# K60_main.net
KiCad netlist of a schematic drawn in Altium Designer
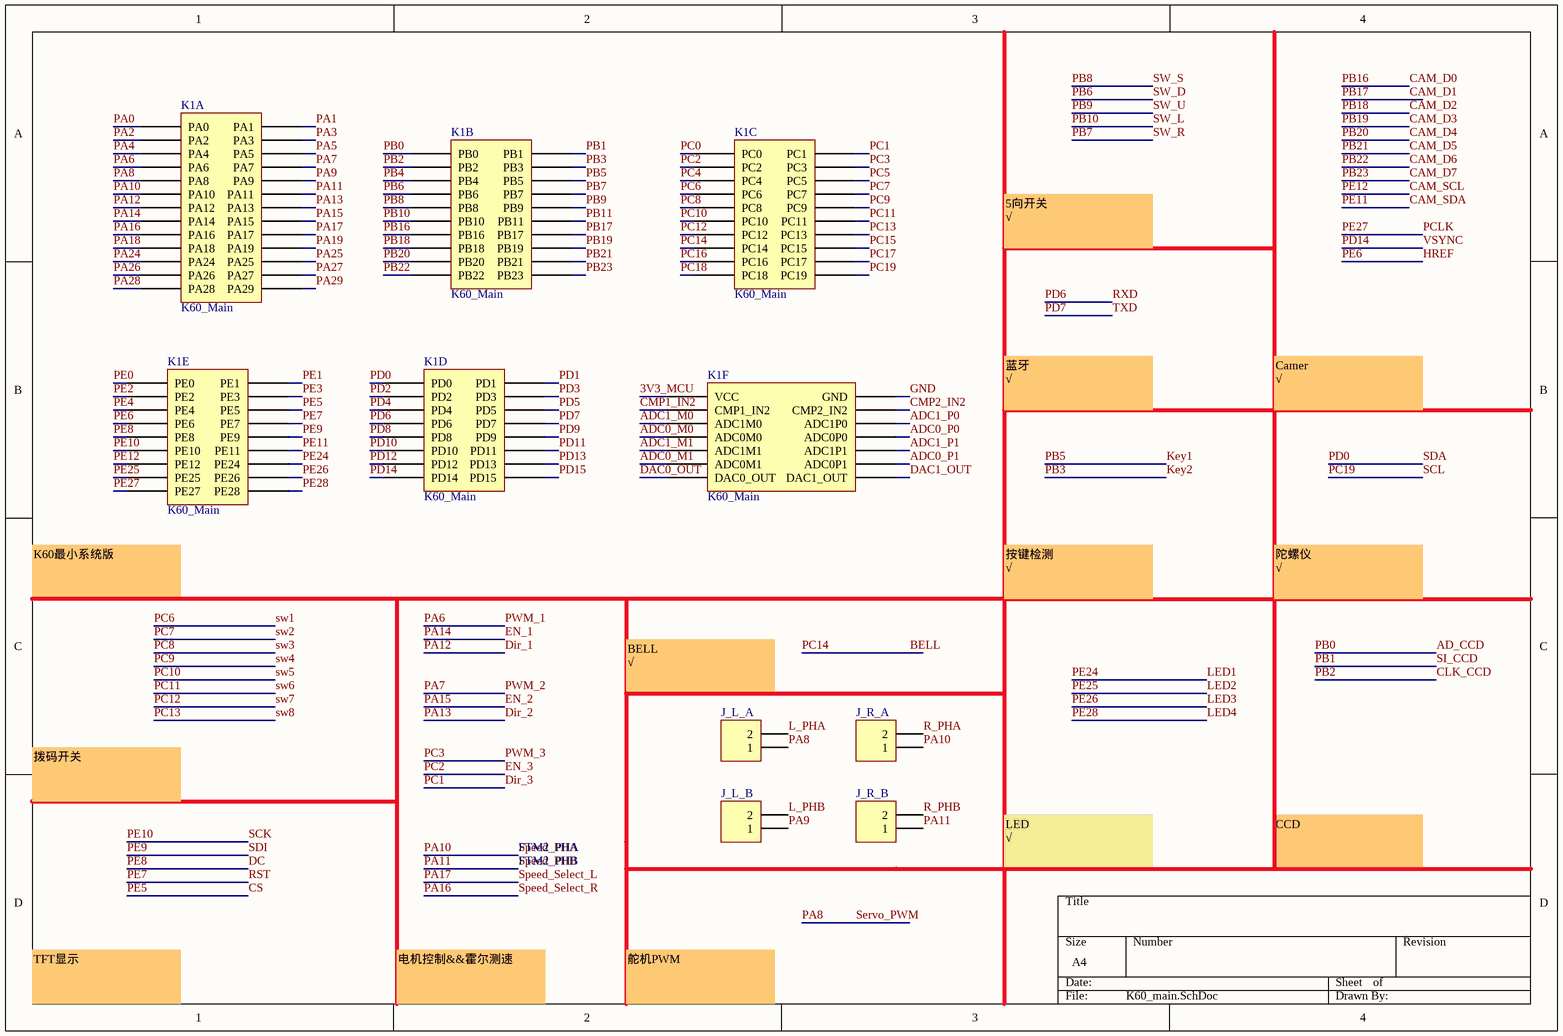
[diagram p0: K60_main.SchDoc]

(export (version "E")
  (design (tool "Eeschema 10.0.6"))
  (components
    (comp (ref "J_L_A")
      (value "Header 2")
      (footprint "HDR1X2")
      (description "Header, 2-Pin")
      (fields (field (name "PUBLISHER") "Altium Limited"))
      (libsource (lib "Miscellaneous Connectors") (part "Header 2"))
    )
    (comp (ref "J_L_B")
      (value "Header 2")
      (footprint "HDR1X2")
      (description "Header, 2-Pin")
      (fields (field (name "PUBLISHER") "Altium Limited"))
      (libsource (lib "Miscellaneous Connectors") (part "Header 2"))
    )
    (comp (ref "J_R_A")
      (value "Header 2")
      (footprint "HDR1X2")
      (description "Header, 2-Pin")
      (fields (field (name "PUBLISHER") "Altium Limited"))
      (libsource (lib "Miscellaneous Connectors") (part "Header 2"))
    )
    (comp (ref "J_R_B")
      (value "Header 2")
      (footprint "HDR1X2")
      (description "Header, 2-Pin")
      (fields (field (name "PUBLISHER") "Altium Limited"))
      (libsource (lib "Miscellaneous Connectors") (part "Header 2"))
    )
    (comp (ref "K1")
      (value "K60_Main")
      (footprint "K60_Main_Board")
      (libsource (lib "lichao_Library") (part "K60_Main"))
    )
  )
  (nets
    (net (code "1") (name "/3V3_MCU") (class "Default")
      (node (ref "K1") (pin "11") (pinfunction "VCC_11") (pintype "passive"))
    )
    (net (code "2") (name "/ADC0_M0") (class "Default")
      (node (ref "K1") (pin "23") (pinfunction "ADC0M0_23") (pintype "passive"))
    )
    (net (code "3") (name "/ADC0_M1") (class "Default")
      (node (ref "K1") (pin "27") (pinfunction "ADC0M1_27") (pintype "passive"))
    )
    (net (code "4") (name "/ADC0_P0") (class "Default")
      (node (ref "K1") (pin "24") (pinfunction "ADC0P0_24") (pintype "passive"))
    )
    (net (code "5") (name "/ADC0_P1") (class "Default")
      (node (ref "K1") (pin "28") (pinfunction "ADC0P1_28") (pintype "passive"))
    )
    (net (code "6") (name "/ADC1_M0") (class "Default")
      (node (ref "K1") (pin "21") (pinfunction "ADC1M0_21") (pintype "passive"))
    )
    (net (code "7") (name "/ADC1_M1") (class "Default")
      (node (ref "K1") (pin "25") (pinfunction "ADC1M1_25") (pintype "passive"))
    )
    (net (code "8") (name "/ADC1_P0") (class "Default")
      (node (ref "K1") (pin "22") (pinfunction "ADC1P0_22") (pintype "passive"))
    )
    (net (code "9") (name "/ADC1_P1") (class "Default")
      (node (ref "K1") (pin "26") (pinfunction "ADC1P1_26") (pintype "passive"))
    )
    (net (code "10") (name "/AD_CCD") (class "Default")
      (node (ref "K1") (pin "49") (pinfunction "PB0_49") (pintype "passive"))
    )
    (net (code "11") (name "/BELL") (class "Default")
      (node (ref "K1") (pin "35") (pinfunction "PC14_35") (pintype "passive"))
    )
    (net (code "12") (name "/CAM_D0") (class "Default")
      (node (ref "K1") (pin "327") (pinfunction "PB16_327") (pintype "passive"))
    )
    (net (code "13") (name "/CAM_D1") (class "Default")
      (node (ref "K1") (pin "326") (pinfunction "PB17_326") (pintype "passive"))
    )
    (net (code "14") (name "/CAM_D2") (class "Default")
      (node (ref "K1") (pin "325") (pinfunction "PB18_325") (pintype "passive"))
    )
    (net (code "15") (name "/CAM_D3") (class "Default")
      (node (ref "K1") (pin "324") (pinfunction "PB19_324") (pintype "passive"))
    )
    (net (code "16") (name "/CAM_D4") (class "Default")
      (node (ref "K1") (pin "323") (pinfunction "PB20_323") (pintype "passive"))
    )
    (net (code "17") (name "/CAM_D5") (class "Default")
      (node (ref "K1") (pin "322") (pinfunction "PB21_322") (pintype "passive"))
    )
    (net (code "18") (name "/CAM_D6") (class "Default")
      (node (ref "K1") (pin "321") (pinfunction "PB22_321") (pintype "passive"))
    )
    (net (code "19") (name "/CAM_D7") (class "Default")
      (node (ref "K1") (pin "320") (pinfunction "PB23_320") (pintype "passive"))
    )
    (net (code "20") (name "/CAM_SCL") (class "Default")
      (node (ref "K1") (pin "29") (pinfunction "PE12_29") (pintype "passive"))
    )
    (net (code "21") (name "/CAM_SDA") (class "Default")
      (node (ref "K1") (pin "210") (pinfunction "PE11_210") (pintype "passive"))
    )
    (net (code "22") (name "/CLK_CCD") (class "Default")
      (node (ref "K1") (pin "47") (pinfunction "PB2_47") (pintype "passive"))
    )
    (net (code "23") (name "/CMP1_IN2") (class "Default")
      (node (ref "K1") (pin "13") (pinfunction "CMP1_IN2_13") (pintype "passive"))
    )
    (net (code "24") (name "/CMP2_IN2") (class "Default")
      (node (ref "K1") (pin "14") (pinfunction "CMP2_IN2_14") (pintype "passive"))
    )
    (net (code "25") (name "/CS") (class "Default")
      (node (ref "K1") (pin "216") (pinfunction "PE5_216") (pintype "passive"))
    )
    (net (code "26") (name "/DAC0_OUT") (class "Default")
      (node (ref "K1") (pin "54") (pinfunction "DAC0_OUT_54") (pintype "passive"))
    )
    (net (code "27") (name "/DAC1_OUT") (class "Default")
      (node (ref "K1") (pin "53") (pinfunction "DAC1_OUT_53") (pintype "passive"))
    )
    (net (code "28") (name "/DC") (class "Default")
      (node (ref "K1") (pin "213") (pinfunction "PE8_213") (pintype "passive"))
    )
    (net (code "29") (name "/Dir_1") (class "Default")
      (node (ref "K1") (pin "423") (pinfunction "PA12_423") (pintype "passive"))
    )
    (net (code "30") (name "/Dir_2") (class "Default")
      (node (ref "K1") (pin "422") (pinfunction "PA13_422") (pintype "passive"))
    )
    (net (code "31") (name "/Dir_3") (class "Default")
      (node (ref "K1") (pin "318") (pinfunction "PC1_318") (pintype "passive"))
    )
    (net (code "32") (name "/EN_1") (class "Default")
      (node (ref "K1") (pin "421") (pinfunction "PA14_421") (pintype "passive"))
    )
    (net (code "33") (name "/EN_2") (class "Default")
      (node (ref "K1") (pin "420") (pinfunction "PA15_420") (pintype "passive"))
    )
    (net (code "34") (name "/EN_3") (class "Default")
      (node (ref "K1") (pin "317") (pinfunction "PC2_317") (pintype "passive"))
    )
    (net (code "35") (name "/GND") (class "Default")
      (node (ref "K1") (pin "12") (pinfunction "GND_12") (pintype "passive"))
    )
    (net (code "36") (name "/HREF") (class "Default")
      (node (ref "K1") (pin "215") (pinfunction "PE6_215") (pintype "passive"))
    )
    (net (code "37") (name "/Key1") (class "Default")
      (node (ref "K1") (pin "44") (pinfunction "PB5_44") (pintype "passive"))
    )
    (net (code "38") (name "/Key2") (class "Default")
      (node (ref "K1") (pin "46") (pinfunction "PB3_46") (pintype "passive"))
    )
    (net (code "39") (name "/LED1") (class "Default")
      (node (ref "K1") (pin "52") (pinfunction "PE24_52") (pintype "passive"))
    )
    (net (code "40") (name "/LED2") (class "Default")
      (node (ref "K1") (pin "51") (pinfunction "PE25_51") (pintype "passive"))
    )
    (net (code "41") (name "/LED3") (class "Default")
      (node (ref "K1") (pin "438") (pinfunction "PE26_438") (pintype "passive"))
    )
    (net (code "42") (name "/LED4") (class "Default")
      (node (ref "K1") (pin "436") (pinfunction "PE28_436") (pintype "passive"))
    )
    (net (code "43") (name "/L_PHA") (class "Default")
      (node (ref "J_L_A") (pin "2") (pinfunction "2_2") (pintype "passive"))
    )
    (net (code "44") (name "/L_PHB") (class "Default")
      (node (ref "J_L_B") (pin "2") (pinfunction "2_2") (pintype "passive"))
    )
    (net (code "45") (name "/PA0") (class "Default")
      (node (ref "K1") (pin "435") (pinfunction "PA0_435") (pintype "passive"))
    )
    (net (code "46") (name "/PA1") (class "Default")
      (node (ref "K1") (pin "434") (pinfunction "PA1_434") (pintype "passive"))
    )
    (net (code "47") (name "/PA2") (class "Default")
      (node (ref "K1") (pin "433") (pinfunction "PA2_433") (pintype "passive"))
    )
    (net (code "48") (name "/PA3") (class "Default")
      (node (ref "K1") (pin "432") (pinfunction "PA3_432") (pintype "passive"))
    )
    (net (code "49") (name "/PA4") (class "Default")
      (node (ref "K1") (pin "431") (pinfunction "PA4_431") (pintype "passive"))
    )
    (net (code "50") (name "/PA5") (class "Default")
      (node (ref "K1") (pin "430") (pinfunction "PA5_430") (pintype "passive"))
    )
    (net (code "51") (name "/PA6") (class "Default")
      (node (ref "K1") (pin "429") (pinfunction "PA6_429") (pintype "passive"))
    )
    (net (code "52") (name "/PA7") (class "Default")
      (node (ref "K1") (pin "428") (pinfunction "PA7_428") (pintype "passive"))
    )
    (net (code "53") (name "/PA8") (class "Default")
      (node (ref "J_L_A") (pin "1") (pinfunction "1_1") (pintype "passive"))
      (node (ref "K1") (pin "427") (pinfunction "PA8_427") (pintype "passive"))
    )
    (net (code "54") (name "/PA9") (class "Default")
      (node (ref "J_L_B") (pin "1") (pinfunction "1_1") (pintype "passive"))
      (node (ref "K1") (pin "426") (pinfunction "PA9_426") (pintype "passive"))
    )
    (net (code "55") (name "/PA10") (class "Default")
      (node (ref "J_R_A") (pin "1") (pinfunction "1_1") (pintype "passive"))
      (node (ref "K1") (pin "425") (pinfunction "PA10_425") (pintype "passive"))
    )
    (net (code "56") (name "/PA11") (class "Default")
      (node (ref "J_R_B") (pin "1") (pinfunction "1_1") (pintype "passive"))
      (node (ref "K1") (pin "424") (pinfunction "PA11_424") (pintype "passive"))
    )
    (net (code "57") (name "/PA16") (class "Default")
      (node (ref "K1") (pin "419") (pinfunction "PA16_419") (pintype "passive"))
    )
    (net (code "58") (name "/PA17") (class "Default")
      (node (ref "K1") (pin "418") (pinfunction "PA17_418") (pintype "passive"))
    )
    (net (code "59") (name "/PA18") (class "Default")
      (node (ref "K1") (pin "417") (pinfunction "PA18_417") (pintype "passive"))
    )
    (net (code "60") (name "/PA19") (class "Default")
      (node (ref "K1") (pin "416") (pinfunction "PA19_416") (pintype "passive"))
    )
    (net (code "61") (name "/PA24") (class "Default")
      (node (ref "K1") (pin "415") (pinfunction "PA24_415") (pintype "passive"))
    )
    (net (code "62") (name "/PA25") (class "Default")
      (node (ref "K1") (pin "414") (pinfunction "PA25_414") (pintype "passive"))
    )
    (net (code "63") (name "/PA26") (class "Default")
      (node (ref "K1") (pin "413") (pinfunction "PA26_413") (pintype "passive"))
    )
    (net (code "64") (name "/PA27") (class "Default")
      (node (ref "K1") (pin "412") (pinfunction "PA27_412") (pintype "passive"))
    )
    (net (code "65") (name "/PA28") (class "Default")
      (node (ref "K1") (pin "411") (pinfunction "PA28_411") (pintype "passive"))
    )
    (net (code "66") (name "/PA29") (class "Default")
      (node (ref "K1") (pin "410") (pinfunction "PA29_410") (pintype "passive"))
    )
    (net (code "67") (name "/PB1") (class "Default")
      (node (ref "K1") (pin "48") (pinfunction "PB1_48") (pintype "passive"))
    )
    (net (code "68") (name "/PB4") (class "Default")
      (node (ref "K1") (pin "45") (pinfunction "PB4_45") (pintype "passive"))
    )
    (net (code "69") (name "/PB6") (class "Default")
      (node (ref "K1") (pin "43") (pinfunction "PB6_43") (pintype "passive"))
    )
    (net (code "70") (name "/PB7") (class "Default")
      (node (ref "K1") (pin "42") (pinfunction "PB7_42") (pintype "passive"))
    )
    (net (code "71") (name "/PB8") (class "Default")
      (node (ref "K1") (pin "41") (pinfunction "PB8_41") (pintype "passive"))
    )
    (net (code "72") (name "/PB9") (class "Default")
      (node (ref "K1") (pin "330") (pinfunction "PB9_330") (pintype "passive"))
    )
    (net (code "73") (name "/PB10") (class "Default")
      (node (ref "K1") (pin "329") (pinfunction "PB10_329") (pintype "passive"))
    )
    (net (code "74") (name "/PB11") (class "Default")
      (node (ref "K1") (pin "328") (pinfunction "PB11_328") (pintype "passive"))
    )
    (net (code "75") (name "/PC0") (class "Default")
      (node (ref "K1") (pin "319") (pinfunction "PC0_319") (pintype "passive"))
    )
    (net (code "76") (name "/PC3") (class "Default")
      (node (ref "K1") (pin "316") (pinfunction "PC3_316") (pintype "passive"))
    )
    (net (code "77") (name "/PC4") (class "Default")
      (node (ref "K1") (pin "315") (pinfunction "PC4_315") (pintype "passive"))
    )
    (net (code "78") (name "/PC5") (class "Default")
      (node (ref "K1") (pin "314") (pinfunction "PC5_314") (pintype "passive"))
    )
    (net (code "79") (name "/PC6") (class "Default")
      (node (ref "K1") (pin "313") (pinfunction "PC6_313") (pintype "passive"))
    )
    (net (code "80") (name "/PC7") (class "Default")
      (node (ref "K1") (pin "312") (pinfunction "PC7_312") (pintype "passive"))
    )
    (net (code "81") (name "/PC8") (class "Default")
      (node (ref "K1") (pin "311") (pinfunction "PC8_311") (pintype "passive"))
    )
    (net (code "82") (name "/PC9") (class "Default")
      (node (ref "K1") (pin "310") (pinfunction "PC9_310") (pintype "passive"))
    )
    (net (code "83") (name "/PC10") (class "Default")
      (node (ref "K1") (pin "39") (pinfunction "PC10_39") (pintype "passive"))
    )
    (net (code "84") (name "/PC11") (class "Default")
      (node (ref "K1") (pin "38") (pinfunction "PC11_38") (pintype "passive"))
    )
    (net (code "85") (name "/PC12") (class "Default")
      (node (ref "K1") (pin "37") (pinfunction "PC12_37") (pintype "passive"))
    )
    (net (code "86") (name "/PC13") (class "Default")
      (node (ref "K1") (pin "36") (pinfunction "PC13_36") (pintype "passive"))
    )
    (net (code "87") (name "/PC15") (class "Default")
      (node (ref "K1") (pin "34") (pinfunction "PC15_34") (pintype "passive"))
    )
    (net (code "88") (name "/PC16") (class "Default")
      (node (ref "K1") (pin "33") (pinfunction "PC16_33") (pintype "passive"))
    )
    (net (code "89") (name "/PC17") (class "Default")
      (node (ref "K1") (pin "32") (pinfunction "PC17_32") (pintype "passive"))
    )
    (net (code "90") (name "/PC18") (class "Default")
      (node (ref "K1") (pin "31") (pinfunction "PC18_31") (pintype "passive"))
    )
    (net (code "91") (name "/PC19") (class "Default")
      (node (ref "K1") (pin "238") (pinfunction "PC19_238") (pintype "passive"))
    )
    (net (code "92") (name "/PCLK") (class "Default")
      (node (ref "K1") (pin "437") (pinfunction "PE27_437") (pintype "passive"))
    )
    (net (code "93") (name "/PD0") (class "Default")
      (node (ref "K1") (pin "237") (pinfunction "PD0_237") (pintype "passive"))
    )
    (net (code "94") (name "/PD1") (class "Default")
      (node (ref "K1") (pin "236") (pinfunction "PD1_236") (pintype "passive"))
    )
    (net (code "95") (name "/PD2") (class "Default")
      (node (ref "K1") (pin "235") (pinfunction "PD2_235") (pintype "passive"))
    )
    (net (code "96") (name "/PD3") (class "Default")
      (node (ref "K1") (pin "234") (pinfunction "PD3_234") (pintype "passive"))
    )
    (net (code "97") (name "/PD4") (class "Default")
      (node (ref "K1") (pin "233") (pinfunction "PD4_233") (pintype "passive"))
    )
    (net (code "98") (name "/PD5") (class "Default")
      (node (ref "K1") (pin "232") (pinfunction "PD5_232") (pintype "passive"))
    )
    (net (code "99") (name "/PD6") (class "Default")
      (node (ref "K1") (pin "231") (pinfunction "PD6_231") (pintype "passive"))
    )
    (net (code "100") (name "/PD7") (class "Default")
      (node (ref "K1") (pin "230") (pinfunction "PD7_230") (pintype "passive"))
    )
    (net (code "101") (name "/PD8") (class "Default")
      (node (ref "K1") (pin "229") (pinfunction "PD8_229") (pintype "passive"))
    )
    (net (code "102") (name "/PD9") (class "Default")
      (node (ref "K1") (pin "228") (pinfunction "PD9_228") (pintype "passive"))
    )
    (net (code "103") (name "/PD10") (class "Default")
      (node (ref "K1") (pin "227") (pinfunction "PD10_227") (pintype "passive"))
    )
    (net (code "104") (name "/PD11") (class "Default")
      (node (ref "K1") (pin "226") (pinfunction "PD11_226") (pintype "passive"))
    )
    (net (code "105") (name "/PD12") (class "Default")
      (node (ref "K1") (pin "225") (pinfunction "PD12_225") (pintype "passive"))
    )
    (net (code "106") (name "/PD13") (class "Default")
      (node (ref "K1") (pin "224") (pinfunction "PD13_224") (pintype "passive"))
    )
    (net (code "107") (name "/PD14") (class "Default")
      (node (ref "K1") (pin "223") (pinfunction "PD14_223") (pintype "passive"))
    )
    (net (code "108") (name "/PD15") (class "Default")
      (node (ref "K1") (pin "222") (pinfunction "PD15_222") (pintype "passive"))
    )
    (net (code "109") (name "/PE0") (class "Default")
      (node (ref "K1") (pin "221") (pinfunction "PE0_221") (pintype "passive"))
    )
    (net (code "110") (name "/PE1") (class "Default")
      (node (ref "K1") (pin "220") (pinfunction "PE1_220") (pintype "passive"))
    )
    (net (code "111") (name "/PE2") (class "Default")
      (node (ref "K1") (pin "219") (pinfunction "PE2_219") (pintype "passive"))
    )
    (net (code "112") (name "/PE3") (class "Default")
      (node (ref "K1") (pin "218") (pinfunction "PE3_218") (pintype "passive"))
    )
    (net (code "113") (name "/PE4") (class "Default")
      (node (ref "K1") (pin "217") (pinfunction "PE4_217") (pintype "passive"))
    )
    (net (code "114") (name "/PE7") (class "Default")
      (node (ref "K1") (pin "214") (pinfunction "PE7_214") (pintype "passive"))
    )
    (net (code "115") (name "/PE9") (class "Default")
      (node (ref "K1") (pin "212") (pinfunction "PE9_212") (pintype "passive"))
    )
    (net (code "116") (name "/PE10") (class "Default")
      (node (ref "K1") (pin "211") (pinfunction "PE10_211") (pintype "passive"))
    )
    (net (code "117") (name "/R_PHA") (class "Default")
      (node (ref "J_R_A") (pin "2") (pinfunction "2_2") (pintype "passive"))
    )
    (net (code "118") (name "/R_PHB") (class "Default")
      (node (ref "J_R_B") (pin "2") (pinfunction "2_2") (pintype "passive"))
    )
  )
)
